# IC555_Timer.net
KiCad netlist of a schematic drawn in EAGLE
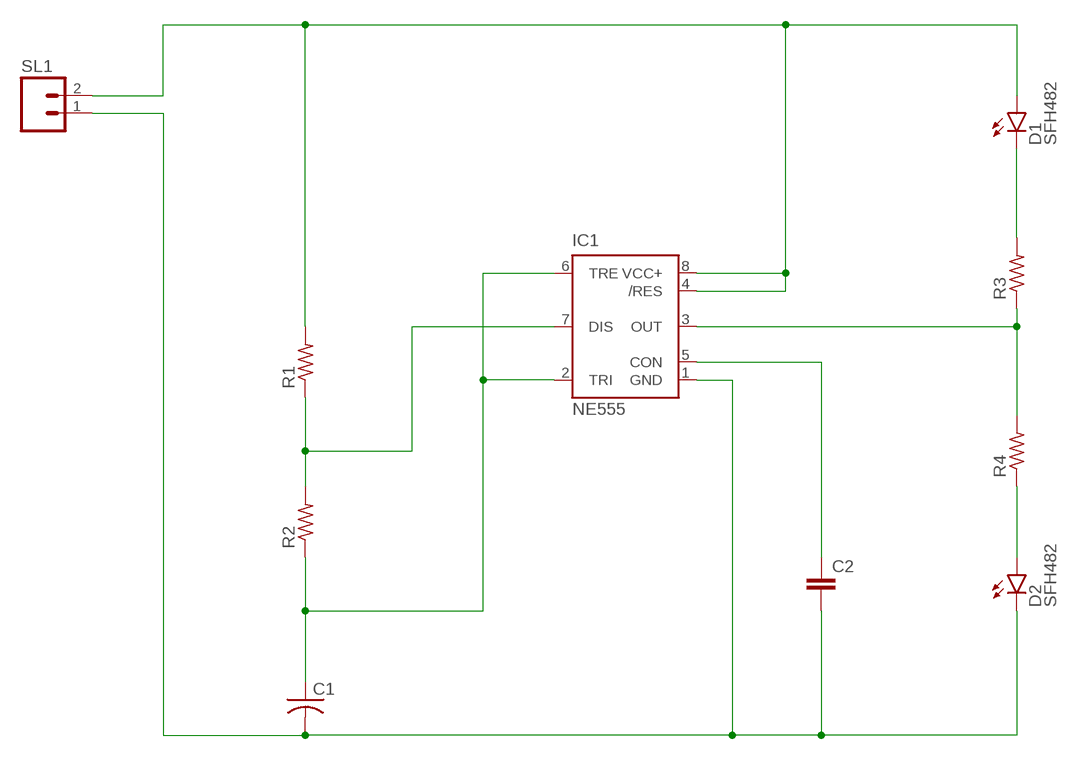
[diagram p0: schematic, sheet 1]

(export (version "E")
  (design (tool "Eeschema 10.0.6"))
  (components
    (comp (ref "C1")
      (value "C-US025-030X050")
      (footprint "eagle-import:C025-030X050")
      (libsource (lib "eagle-import") (part "C-US025-030X050"))
    )
    (comp (ref "C2")
      (value "C-EU025-024X044")
      (footprint "eagle-import:C025-024X044")
      (libsource (lib "eagle-import") (part "C-EU025-024X044"))
    )
    (comp (ref "D1")
      (value "SFH482")
      (footprint "eagle-import:SFH482")
      (libsource (lib "eagle-import") (part "SFH482"))
    )
    (comp (ref "D2")
      (value "SFH482")
      (footprint "eagle-import:SFH482")
      (libsource (lib "eagle-import") (part "SFH482"))
    )
    (comp (ref "IC1")
      (value "NE555")
      (footprint "eagle-import:DIL-08")
      (fields (field (name "MF") "Arrow Electronics") (field (name "MPN") "NE555N"))
      (libsource (lib "eagle-import") (part "NE555"))
    )
    (comp (ref "R1")
      (value "R-US_0204/5")
      (footprint "eagle-import:0204_5")
      (libsource (lib "eagle-import") (part "R-US_0204/5"))
    )
    (comp (ref "R2")
      (value "R-US_0204/5")
      (footprint "eagle-import:0204_5")
      (libsource (lib "eagle-import") (part "R-US_0204/5"))
    )
    (comp (ref "R3")
      (value "R-US_0204/5")
      (footprint "eagle-import:0204_5")
      (libsource (lib "eagle-import") (part "R-US_0204/5"))
    )
    (comp (ref "R4")
      (value "R-US_0204/5")
      (footprint "eagle-import:0204_5")
      (libsource (lib "eagle-import") (part "R-US_0204/5"))
    )
    (comp (ref "SL1")
      (value "M02")
      (footprint "eagle-import:02P")
      (libsource (lib "eagle-import") (part "M02"))
    )
  )
  (nets
    (net (code "1") (name "Net-(D1-C)") (class "Default")
      (node (ref "D1") (pin "K") (pinfunction "C_K") (pintype "passive"))
      (node (ref "R3") (pin "2") (pinfunction "2_2") (pintype "passive"))
    )
    (net (code "2") (name "Net-(D2-C)") (class "Default")
      (node (ref "C1") (pin "2") (pinfunction "2_2") (pintype "passive"))
      (node (ref "C2") (pin "2") (pinfunction "2_2") (pintype "passive"))
      (node (ref "D2") (pin "K") (pinfunction "C_K") (pintype "passive"))
      (node (ref "IC1") (pin "1") (pinfunction "GND_1") (pintype "power_in"))
      (node (ref "SL1") (pin "1") (pinfunction "1_1") (pintype "passive"))
    )
    (net (code "3") (name "Net-(D2-PadA)") (class "Default")
      (node (ref "D2") (pin "A") (pinfunction "A_A") (pintype "passive"))
      (node (ref "R4") (pin "1") (pinfunction "1_1") (pintype "passive"))
    )
    (net (code "4") (name "Net-(IC1-CON)") (class "Default")
      (node (ref "C2") (pin "1") (pinfunction "1_1") (pintype "passive"))
      (node (ref "IC1") (pin "5") (pinfunction "CON_5") (pintype "input"))
    )
    (net (code "5") (name "Net-(IC1-DIS)") (class "Default")
      (node (ref "IC1") (pin "7") (pinfunction "DIS_7") (pintype "input"))
      (node (ref "R1") (pin "1") (pinfunction "1_1") (pintype "passive"))
      (node (ref "R2") (pin "2") (pinfunction "2_2") (pintype "passive"))
    )
    (net (code "6") (name "Net-(IC1-OUT)") (class "Default")
      (node (ref "IC1") (pin "3") (pinfunction "OUT_3") (pintype "output"))
      (node (ref "R3") (pin "1") (pinfunction "1_1") (pintype "passive"))
      (node (ref "R4") (pin "2") (pinfunction "2_2") (pintype "passive"))
    )
    (net (code "7") (name "Net-(IC1-TRE)") (class "Default")
      (node (ref "C1") (pin "1") (pinfunction "1_1") (pintype "passive"))
      (node (ref "IC1") (pin "2") (pinfunction "TRI_2") (pintype "input"))
      (node (ref "IC1") (pin "6") (pinfunction "TRE_6") (pintype "input"))
      (node (ref "R2") (pin "1") (pinfunction "1_1") (pintype "passive"))
    )
    (net (code "8") (name "Net-(IC1-VCC+)") (class "Default")
      (node (ref "D1") (pin "A") (pinfunction "A_A") (pintype "passive"))
      (node (ref "IC1") (pin "4") (pinfunction "/RES_4") (pintype "input"))
      (node (ref "IC1") (pin "8") (pinfunction "VCC+_8") (pintype "power_in"))
      (node (ref "R1") (pin "2") (pinfunction "2_2") (pintype "passive"))
      (node (ref "SL1") (pin "2") (pinfunction "2_2") (pintype "passive"))
    )
  )
)
